# design.net
KiCad netlist of a schematic drawn in Altium Designer
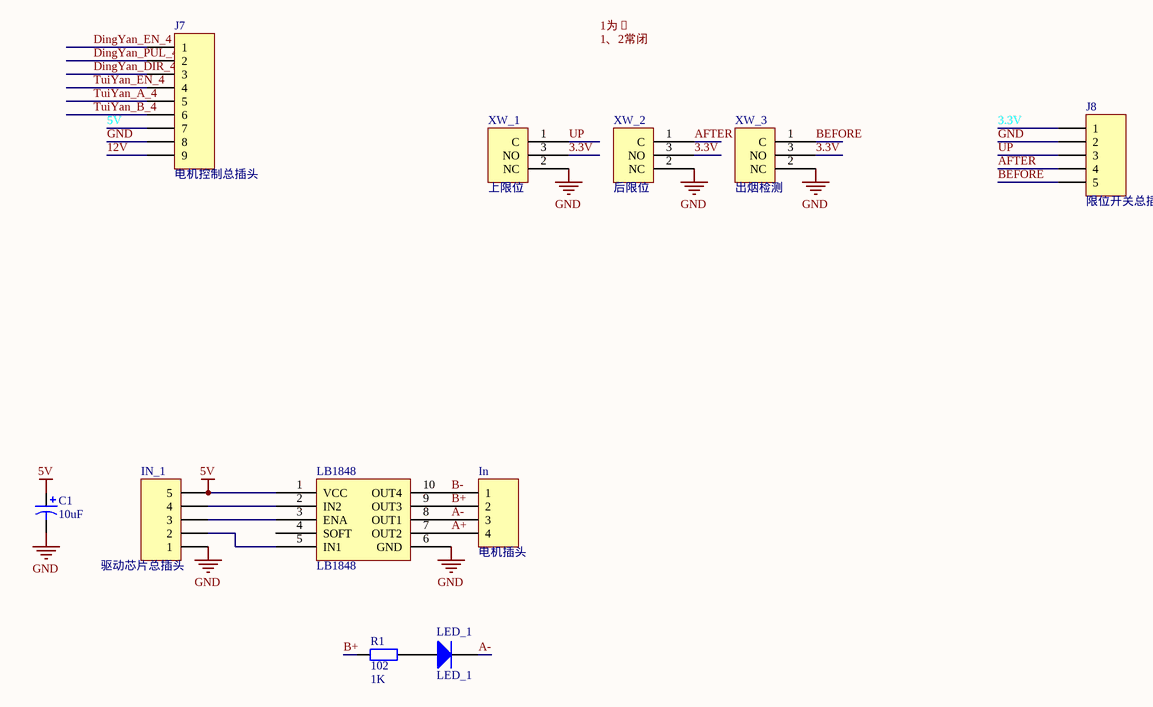
[diagram p0: 售烟机上限位电路板.SchDoc]

(export (version "E")
  (design (tool "Eeschema 10.0.6"))
  (components
    (comp (ref "C1")
      (value "10uF")
      (footprint "有极性电容")
      (description "Polarized Capacitor (Radial)")
      (fields (field (name "Comment") "106C") (field (name "PUBLISHER") "Altium Limited"))
      (libsource (lib "Miscellaneous Devices") (part "Cap Pol1"))
    )
    (comp (ref "In")
      (value "电机插头")
      (footprint "间距1.0mm软排线底座")
      (description "Header, 4-Pin")
      (fields (field (name "PUBLISHER") "Altium Limited"))
      (libsource (lib "Miscellaneous Connectors") (part "MHDR1X4"))
    )
    (comp (ref "IN_1")
      (value "驱动芯片总插头")
      (footprint "HDR1X5")
      (description "Header, 5-Pin")
      (fields (field (name "PUBLISHER") "Altium Limited"))
      (libsource (lib "") (part "Header 5_1"))
    )
    (comp (ref "J7")
      (value "电机控制总插头")
      (footprint "HDR1X9")
      (description "Header, 9-Pin")
      (fields (field (name "PUBLISHER") "Altium Limited"))
      (libsource (lib "Miscellaneous Connectors") (part "Header 9"))
    )
    (comp (ref "J8")
      (value "限位开关总插头")
      (footprint "HDR1X5")
      (description "Header, 5-Pin")
      (fields (field (name "PUBLISHER") "Altium Limited"))
      (libsource (lib "Miscellaneous Connectors") (part "Header 5"))
    )
    (comp (ref "LB1848") (value "LB1848") (footprint "LB1848") (libsource (lib "老罗专用原理图库") (part "LB1848")))
    (comp (ref "LED_1")
      (value "LED_1")
      (footprint "0805")
      (description "Default Diode")
      (fields (field (name "PUBLISHER") "Altium Limited"))
      (libsource (lib "Miscellaneous Devices") (part "Diode"))
    )
    (comp (ref "R1")
      (value "102")
      (footprint "0805")
      (description "Resistor")
      (fields (field (name "ALTIUM_VALUE") "1K") (field (name "PUBLISHER") "Altium Limited"))
      (libsource (lib "Miscellaneous Devices") (part "Res2"))
    )
    (comp (ref "XW_1") (value "上限位") (libsource (lib "老罗专用原理图库") (part "限位开关")))
    (comp (ref "XW_2") (value "后限位") (libsource (lib "老罗专用原理图库") (part "限位开关")))
    (comp (ref "XW_3") (value "出烟检测") (libsource (lib "老罗专用原理图库") (part "限位开关")))
  )
  (nets
    (net (code "3") (name "/3.3V") (class "Default")
      (node (ref "J8") (pin "1") (pinfunction "1_1") (pintype "passive"))
      (node (ref "XW_1") (pin "3") (pinfunction "NO_3") (pintype "passive"))
      (node (ref "XW_2") (pin "3") (pinfunction "NO_3") (pintype "passive"))
      (node (ref "XW_3") (pin "3") (pinfunction "NO_3") (pintype "passive"))
    )
    (net (code "4") (name "/12V") (class "Default")
      (node (ref "J7") (pin "9") (pinfunction "9_9") (pintype "passive"))
    )
    (net (code "5") (name "/A+") (class "Default")
      (node (ref "In") (pin "4") (pinfunction "4_4") (pintype "passive"))
      (node (ref "LB1848") (pin "7") (pinfunction "OUT2_7") (pintype "passive"))
    )
    (net (code "6") (name "/A-") (class "Default")
      (node (ref "In") (pin "3") (pinfunction "3_3") (pintype "passive"))
      (node (ref "LB1848") (pin "8") (pinfunction "OUT1_8") (pintype "passive"))
      (node (ref "LED_1") (pin "2") (pinfunction "K_2") (pintype "passive"))
    )
    (net (code "7") (name "/AFTER") (class "Default")
      (node (ref "J8") (pin "4") (pinfunction "4_4") (pintype "passive"))
      (node (ref "XW_2") (pin "1") (pinfunction "C_1") (pintype "passive"))
    )
    (net (code "8") (name "/B+") (class "Default")
      (node (ref "In") (pin "2") (pinfunction "2_2") (pintype "passive"))
      (node (ref "LB1848") (pin "9") (pinfunction "OUT3_9") (pintype "passive"))
      (node (ref "R1") (pin "1") (pinfunction "1_1") (pintype "passive"))
    )
    (net (code "9") (name "/B-") (class "Default")
      (node (ref "In") (pin "1") (pinfunction "1_1") (pintype "passive"))
      (node (ref "LB1848") (pin "10") (pinfunction "OUT4_10") (pintype "passive"))
    )
    (net (code "10") (name "/BEFORE") (class "Default")
      (node (ref "J8") (pin "5") (pinfunction "5_5") (pintype "passive"))
      (node (ref "XW_3") (pin "1") (pinfunction "C_1") (pintype "passive"))
    )
    (net (code "11") (name "/DingYan_DIR_4") (class "Default")
      (node (ref "J7") (pin "3") (pinfunction "3_3") (pintype "passive"))
    )
    (net (code "12") (name "/DingYan_EN_4") (class "Default")
      (node (ref "J7") (pin "1") (pinfunction "1_1") (pintype "passive"))
    )
    (net (code "13") (name "/DingYan_PUL_4") (class "Default")
      (node (ref "J7") (pin "2") (pinfunction "2_2") (pintype "passive"))
    )
    (net (code "14") (name "/TuiYan_A_4") (class "Default")
      (node (ref "J7") (pin "5") (pinfunction "5_5") (pintype "passive"))
    )
    (net (code "15") (name "/TuiYan_B_4") (class "Default")
      (node (ref "J7") (pin "6") (pinfunction "6_6") (pintype "passive"))
    )
    (net (code "16") (name "/TuiYan_EN_4") (class "Default")
      (node (ref "J7") (pin "4") (pinfunction "4_4") (pintype "passive"))
    )
    (net (code "17") (name "/UP") (class "Default")
      (node (ref "J8") (pin "3") (pinfunction "3_3") (pintype "passive"))
      (node (ref "XW_1") (pin "1") (pinfunction "C_1") (pintype "passive"))
    )
    (net (code "18") (name "5V") (class "Default")
      (node (ref "C1") (pin "1") (pinfunction "1_1") (pintype "passive"))
      (node (ref "IN_1") (pin "5") (pinfunction "5_5") (pintype "passive"))
      (node (ref "J7") (pin "7") (pinfunction "7_7") (pintype "passive"))
      (node (ref "LB1848") (pin "1") (pinfunction "VCC_1") (pintype "passive"))
    )
    (net (code "19") (name "GND") (class "Default")
      (node (ref "C1") (pin "2") (pinfunction "2_2") (pintype "passive"))
      (node (ref "IN_1") (pin "1") (pinfunction "1_1") (pintype "passive"))
      (node (ref "J7") (pin "8") (pinfunction "8_8") (pintype "passive"))
      (node (ref "J8") (pin "2") (pinfunction "2_2") (pintype "passive"))
      (node (ref "LB1848") (pin "6") (pinfunction "GND_6") (pintype "passive"))
      (node (ref "XW_1") (pin "2") (pinfunction "NC_2") (pintype "passive"))
      (node (ref "XW_2") (pin "2") (pinfunction "NC_2") (pintype "passive"))
      (node (ref "XW_3") (pin "2") (pinfunction "NC_2") (pintype "passive"))
    )
    (net (code "20") (name "Net-(LB1848-ENA)") (class "Default")
      (node (ref "IN_1") (pin "3") (pinfunction "3_3") (pintype "passive"))
      (node (ref "LB1848") (pin "3") (pinfunction "ENA_3") (pintype "passive"))
    )
    (net (code "21") (name "Net-(LB1848-IN1)") (class "Default")
      (node (ref "IN_1") (pin "2") (pinfunction "2_2") (pintype "passive"))
      (node (ref "LB1848") (pin "5") (pinfunction "IN1_5") (pintype "passive"))
    )
    (net (code "22") (name "Net-(LB1848-IN2)") (class "Default")
      (node (ref "IN_1") (pin "4") (pinfunction "4_4") (pintype "passive"))
      (node (ref "LB1848") (pin "2") (pinfunction "IN2_2") (pintype "passive"))
    )
    (net (code "23") (name "Net-(LED_1-A)") (class "Default")
      (node (ref "LED_1") (pin "1") (pinfunction "A_1") (pintype "passive"))
      (node (ref "R1") (pin "2") (pinfunction "2_2") (pintype "passive"))
    )
    (net (code "24") (name "unconnected-(LB1848-SOFT-Pad4)") (class "Default")
      (node (ref "LB1848") (pin "4") (pinfunction "SOFT_4") (pintype "passive"))
    )
  )
)
